# 1-3circuits.net
KiCad netlist of a schematic drawn in EasyEDA
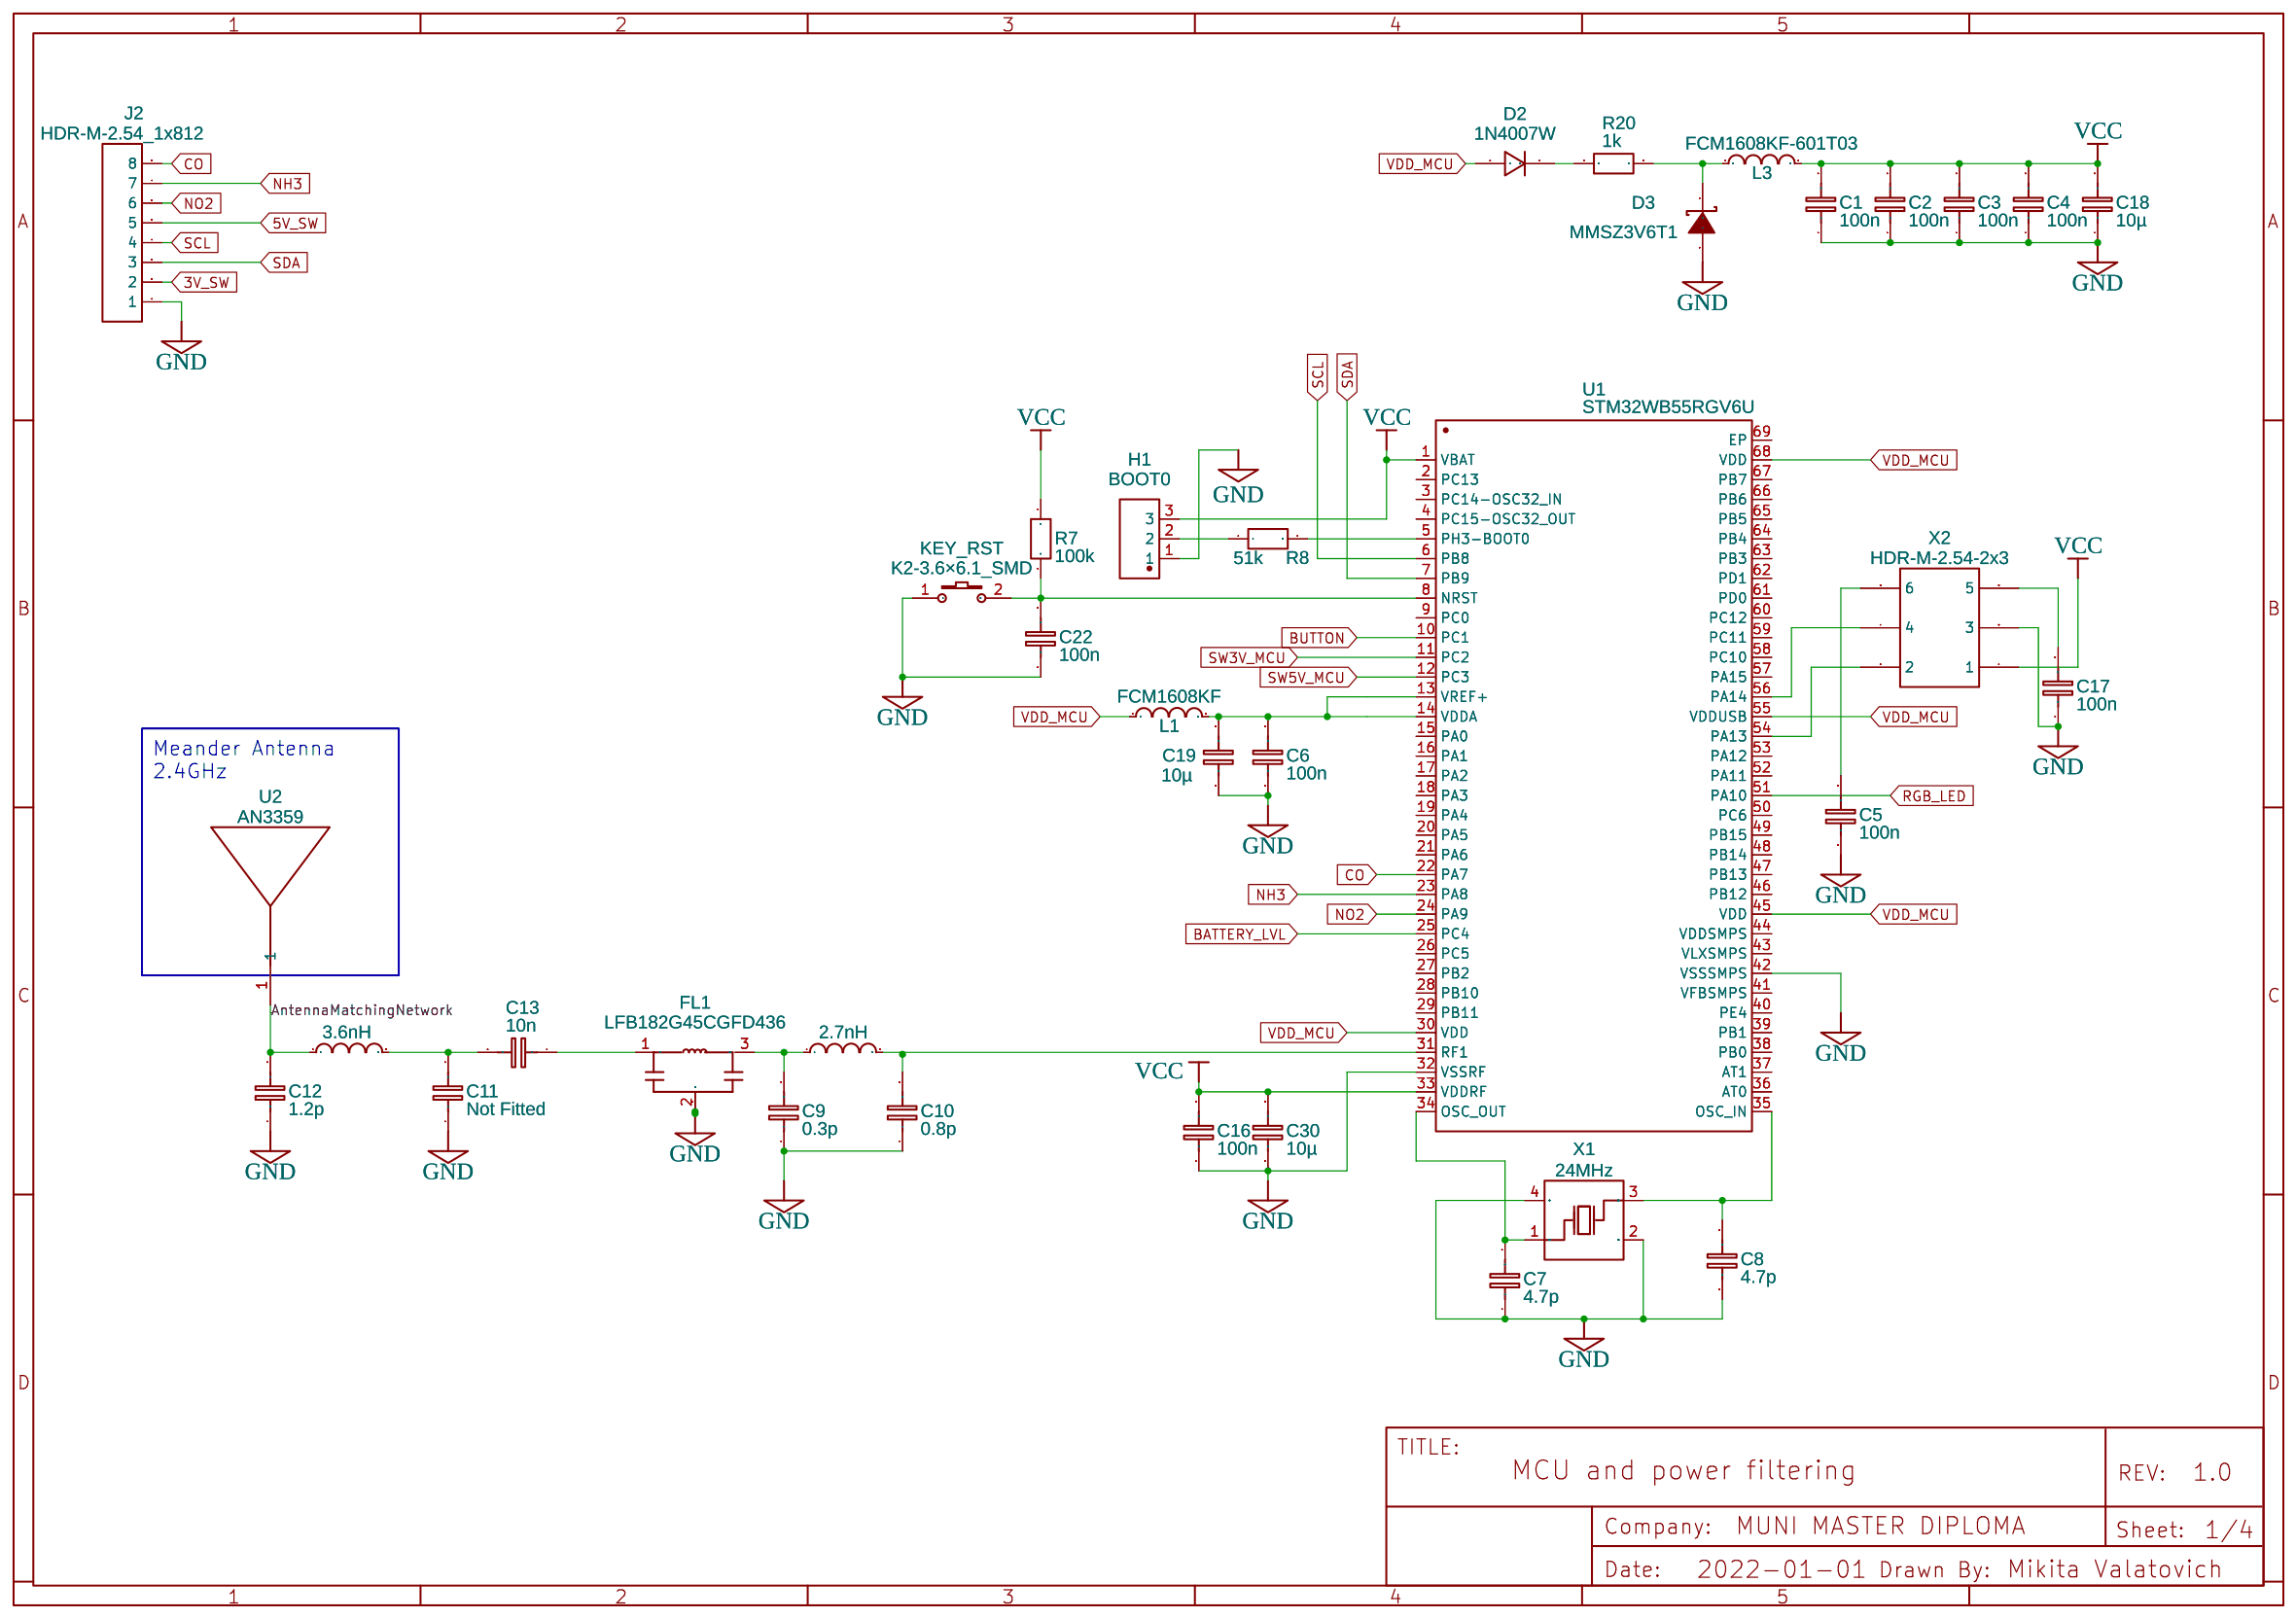
[diagram p0: mcu]
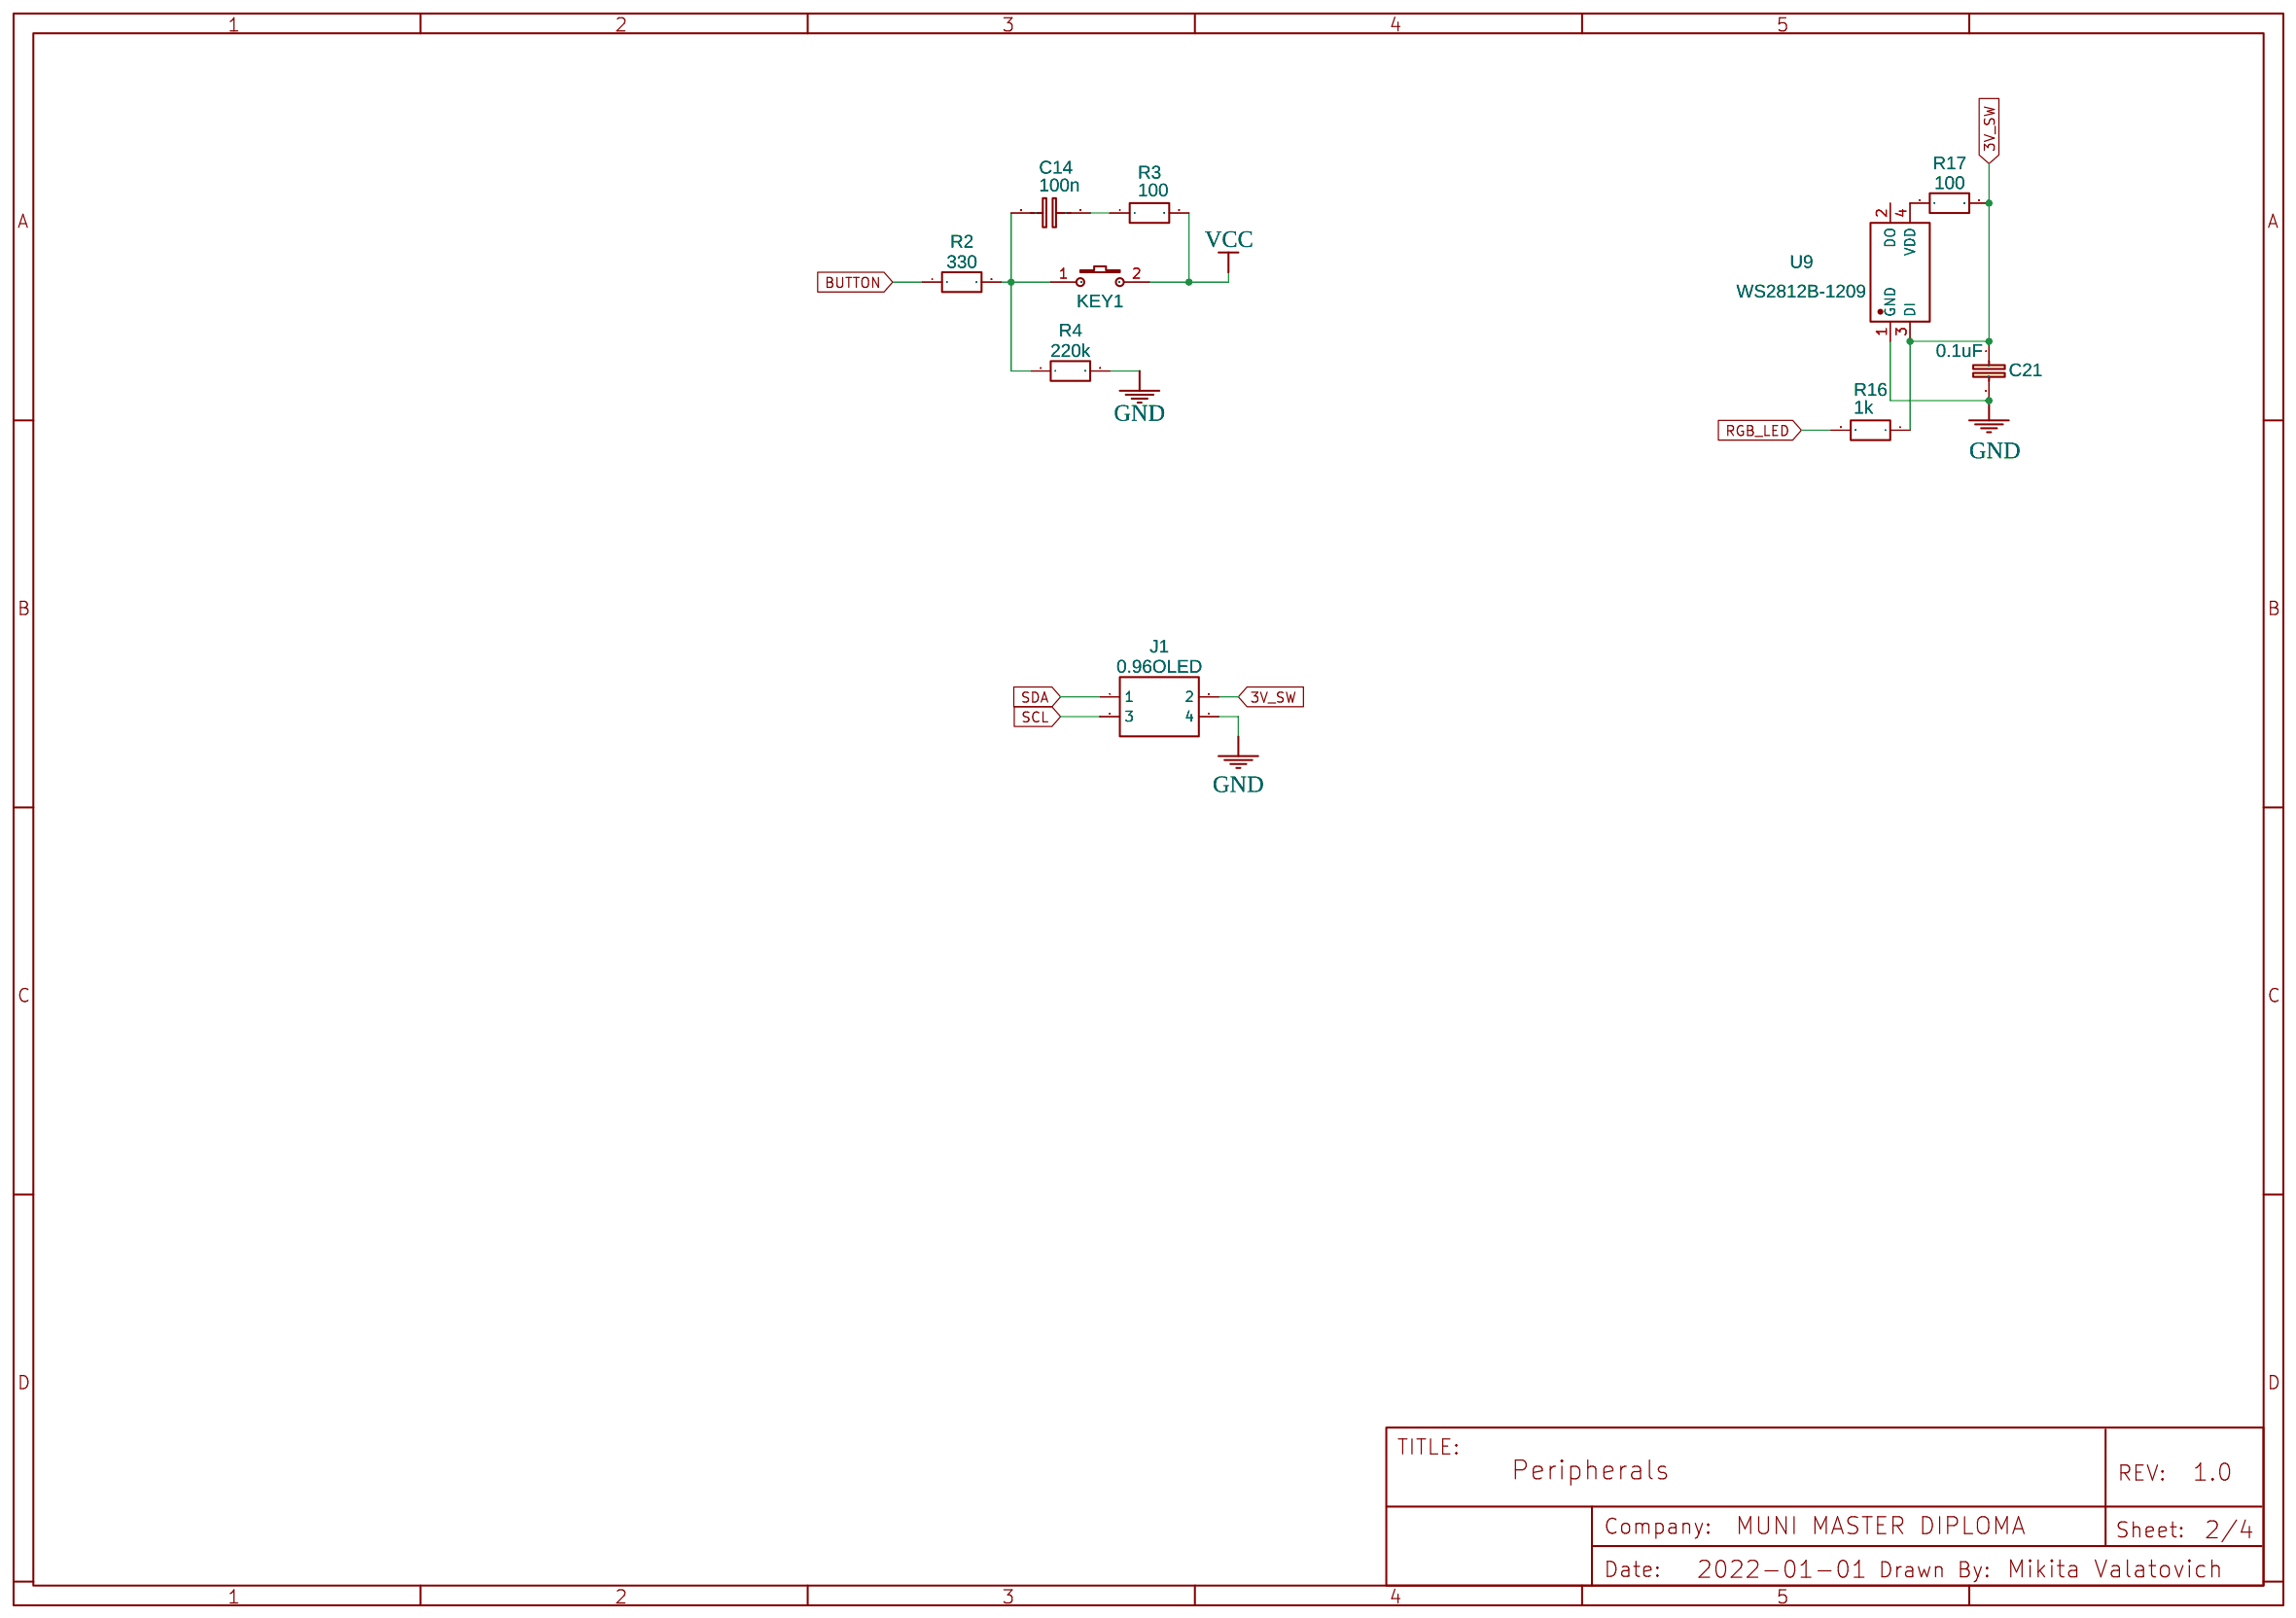
[diagram p1: peripherals]
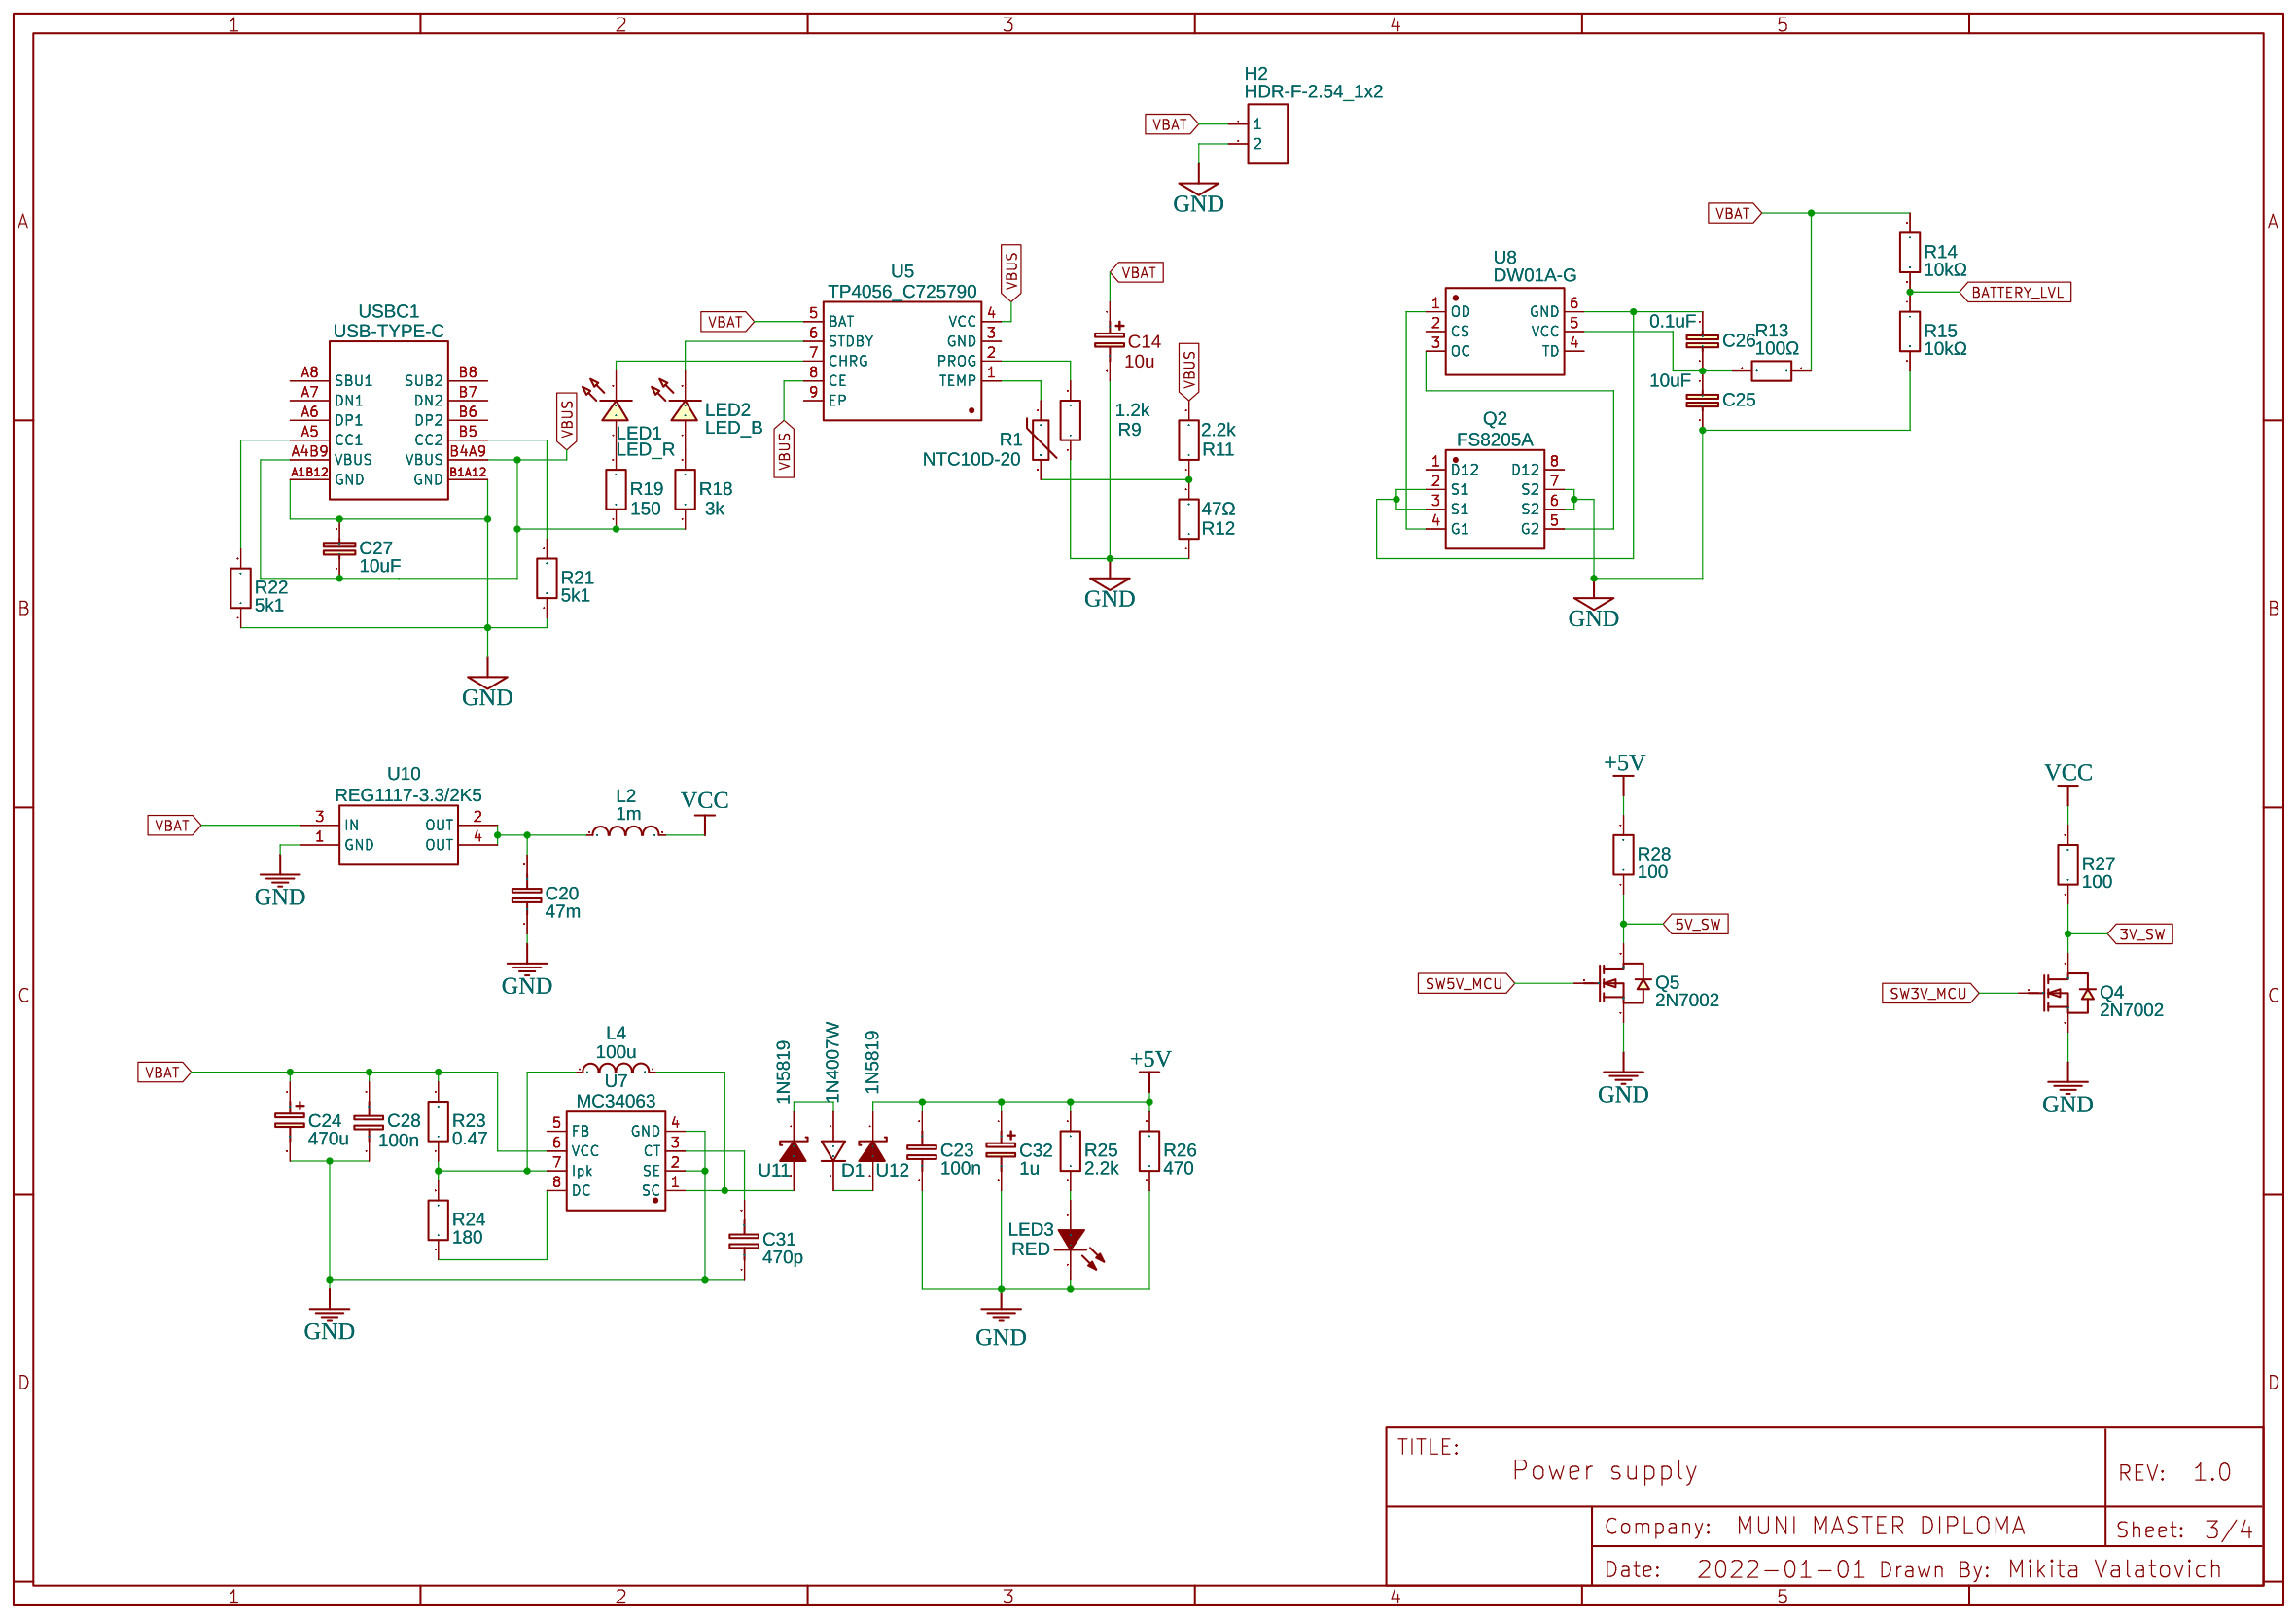
[diagram p2: power_supply]

(export (version "E")
  (design (tool "Eeschema 10.0.6"))
  (components
    (comp (ref "C1") (value "100n") (libsource (lib "") (part "C_0603_EU_1")))
    (comp (ref "C2") (value "100n") (libsource (lib "") (part "C_0603_EU_1")))
    (comp (ref "C3") (value "100n") (libsource (lib "") (part "C_0603_EU_1")))
    (comp (ref "C4") (value "100n") (libsource (lib "") (part "C_0603_EU_1")))
    (comp (ref "C5") (value "100n") (libsource (lib "") (part "C_0603_EU")))
    (comp (ref "C6") (value "100n") (libsource (lib "") (part "C_0603_EU")))
    (comp (ref "C7") (value "4.7p") (libsource (lib "") (part "C_0603_EU")))
    (comp (ref "C8") (value "4.7p") (libsource (lib "") (part "C_0603_EU")))
    (comp (ref "C9") (value "0.3p") (libsource (lib "") (part "C_0603_EU_3")))
    (comp (ref "C10") (value "0.8p") (libsource (lib "") (part "C_0603_EU_3")))
    (comp (ref "C11") (value "Not Fitted") (libsource (lib "") (part "C_0603_EU_3")))
    (comp (ref "C12") (value "1.2p") (libsource (lib "") (part "C_0603_EU_3")))
    (comp (ref "C13") (value "10n") (libsource (lib "") (part "C_0603_EU_2")))
    (comp (ref "C16") (value "100n") (libsource (lib "") (part "C_0603_EU")))
    (comp (ref "C17") (value "100n") (libsource (lib "") (part "C_0603_EU")))
    (comp (ref "C18") (value "10µ") (libsource (lib "") (part "C_0603_EU_1")))
    (comp (ref "C19") (value "10µ") (libsource (lib "") (part "C_0603_EU")))
    (comp (ref "C22") (value "100n") (libsource (lib "") (part "C_0603_EU")))
    (comp (ref "C30") (value "10µ") (libsource (lib "") (part "C_0603_EU")))
    (comp (ref "D2")
      (value "1N4007W")
      (fields (field (name "BOM_Supplier Part") "C328592"))
      (libsource (lib "") (part "1N4007W"))
    )
    (comp (ref "D3")
      (value "MMSZ3V6T1")
      (fields
        (field (name "BOM_Manufacturer Part") "DIODEZENER3.3V500MWSOD-523")
        (field (name "BOM_Supplier Part") "C9900023612")
      )
      (libsource (lib "") (part "DIODEZENER3.3V500MWSOD-523"))
    )
    (comp (ref "FL1") (value "LFB182G45CGFD436") (libsource (lib "") (part "LFB182G45CGFD436")))
    (comp (ref "H1")
      (value "BOOT0")
      (fields
        (field (name "BOM_Manufacturer Part") "PZ254-1-03-Z-8.5")
        (field (name "BOM_Supplier Part") "C2894926")
      )
      (libsource (lib "") (part "PZ254-1-03-Z-8.5"))
    )
    (comp (ref "J2")
      (value "HDR-M-2.54_1x812")
      (fields (field (name "BOM_Supplier Part") "C190820"))
      (libsource (lib "") (part "HDR-M-2.54_1x812"))
    )
    (comp (ref "KEY_RST")
      (value "K2-3.6×6.1_SMD")
      (fields
        (field (name "BOM_Manufacturer Part") "K2-1107ST-A4SW-06")
        (field (name "BOM_Supplier Part") "C118141")
      )
      (libsource (lib "") (part "K2-3.6×6.1_SMD"))
    )
    (comp (ref "L")
      (value "3.6nH")
      (fields
        (field (name "BOM_Manufacturer Part") "LQG15HS3N6S02D")
        (field (name "BOM_Supplier Part") "81-LQG15HS3N6S02D")
      )
      (libsource (lib "") (part "LQG15HS3N6S02D"))
    )
    (comp (ref "L1")
      (value "FCM1608KF")
      (fields
        (field (name "BOM_Manufacturer Part") "FCM1608KF-601T03")
        (field (name "BOM_Supplier Part") "C141723")
      )
      (libsource (lib "") (part "FCM1608KF-601T03"))
    )
    (comp (ref "L3")
      (value "FCM1608KF-601T03")
      (fields (field (name "BOM_Supplier Part") "C141723"))
      (libsource (lib "") (part "FCM1608KF-601T03"))
    )
    (comp (ref "NO")
      (value "2.7nH")
      (fields
        (field (name "BOM_Manufacturer Part") "LQG15HS2N7S02D")
        (field (name "BOM_Supplier Part") "81-LQG15HS2N7S02D")
      )
      (libsource (lib "") (part "LQG15HS2N7S02D"))
    )
    (comp (ref "R7") (value "100k") (libsource (lib "") (part "R_0603_EU")))
    (comp (ref "R8") (value "51k") (libsource (lib "") (part "R_0603_EU_1")))
    (comp (ref "R20") (value "1k") (libsource (lib "") (part "R_0603_EU_1")))
    (comp (ref "U1")
      (value "STM32WB55RGV6U")
      (fields (field (name "BOM_Supplier Part") "C1558433"))
      (libsource (lib "") (part "STM32WB55RGV6U"))
    )
    (comp (ref "U2") (value "AN3359") (libsource (lib "") (part "AN3359")))
    (comp (ref "X1")
      (value "24MHz")
      (fields
        (field (name "BOM_Manufacturer Part") "ABM8AIG-24.000MHZ-R40-4-T")
        (field (name "BOM_Supplier Part") "C1986620")
      )
      (libsource (lib "") (part "ABM8AIG-24.000MHZ-R40-4-T"))
    )
    (comp (ref "X2") (value "HDR-M-2.54-2x3") (libsource (lib "") (part "HDR-M-2.54-2x3")))
    (comp (ref "C14") (value "100n") (libsource (lib "") (part "C_0603_EU")))
    (comp (ref "C21") (value "0.1uF") (libsource (lib "") (part "0.1UF-25V(+80_-20%)(0603)")))
    (comp (ref "J1")
      (value "0.96OLED")
      (fields (field (name "BOM_Supplier Part") "C66690"))
      (libsource (lib "") (part "HDR-M-2.54_2x2"))
    )
    (comp (ref "KEY1")
      (value "K2-3.6×6.1_SMD")
      (fields
        (field (name "BOM_Manufacturer Part") "K2-1107ST-A4SW-06")
        (field (name "BOM_Supplier Part") "C118141")
      )
      (libsource (lib "") (part "K2-3.6×6.1_SMD"))
    )
    (comp (ref "R2") (value "330") (libsource (lib "") (part "R_0603_EU")))
    (comp (ref "R3") (value "100") (libsource (lib "") (part "R_0603_EU")))
    (comp (ref "R4") (value "220k") (libsource (lib "") (part "R_0603_EU")))
    (comp (ref "R16")
      (value "1k")
      (fields
        (field (name "BOM_Manufacturer Part") "TCTR0603F47K0F3960T")
        (field (name "BOM_Supplier Part") "C525388")
      )
      (libsource (lib "") (part "TCTR0603F47K0F3960T_1"))
    )
    (comp (ref "R17")
      (value "100")
      (fields
        (field (name "BOM_Manufacturer Part") "TCTR0603F47K0F3960T")
        (field (name "BOM_Supplier Part") "C525388")
      )
      (libsource (lib "") (part "TCTR0603F47K0F3960T"))
    )
    (comp (ref "U9")
      (value "WS2812B-1209")
      (fields (field (name "BOM_Supplier Part") "C2835111"))
      (libsource (lib "") (part "WS2812B-1209"))
    )
    (comp (ref "C20") (value "47m") (libsource (lib "") (part "C_0603_EU")))
    (comp (ref "C23") (value "100n") (libsource (lib "") (part "C_0603_EU")))
    (comp (ref "C24") (value "470u") (libsource (lib "") (part "C_Tan_SMD_A_EU_1")))
    (comp (ref "C25") (value "10uF") (libsource (lib "") (part "0.1UF-25V(+80_-20%)(0603)")))
    (comp (ref "C26") (value "0.1uF") (libsource (lib "") (part "0.1UF-25V(+80_-20%)(0603)")))
    (comp (ref "C27") (value "10uF") (libsource (lib "") (part "0.1UF-25V(+80_-20%)(0603)_1")))
    (comp (ref "C28") (value "100n") (libsource (lib "") (part "C_0603_EU")))
    (comp (ref "C31") (value "470p") (libsource (lib "") (part "C_0603_EU")))
    (comp (ref "C32") (value "1u") (libsource (lib "") (part "C_Tan_SMD_A_EU")))
    (comp (ref "D1")
      (value "1N4007W")
      (fields (field (name "BOM_Supplier Part") "C328592"))
      (libsource (lib "") (part "1N4007W"))
    )
    (comp (ref "H2")
      (value "HDR-F-2.54_1x2")
      (fields (field (name "BOM_Supplier Part") "C49661"))
      (libsource (lib "") (part "HDR-F-2.54_1x2"))
    )
    (comp (ref "L2") (value "1m") (libsource (lib "") (part "L0603_US")))
    (comp (ref "L4") (value "100u") (libsource (lib "") (part "L0603_US")))
    (comp (ref "LED1")
      (value "LED_R")
      (fields
        (field (name "BOM_Manufacturer Part") "19-217/R6C-AL1M2VY/3T")
        (field (name "BOM_Supplier Part") "C72044")
      )
      (libsource (lib "") (part "LED-0603_R"))
    )
    (comp (ref "LED2")
      (value "LED_B")
      (fields
        (field (name "BOM_Manufacturer Part") "19-217/BHC-ZL1M2RY/3T")
        (field (name "BOM_Supplier Part") "C72041")
      )
      (libsource (lib "") (part "LED-0603_B"))
    )
    (comp (ref "LED3")
      (value "RED")
      (fields
        (field (name "BOM_Manufacturer Part") "whiteLEDSMD")
        (field (name "BOM_Supplier Part") "C34499")
      )
      (libsource (lib "") (part "whiteLEDSMD"))
    )
    (comp (ref "Q2")
      (value "FS8205A")
      (fields (field (name "BOM_Supplier Part") "C16052"))
      (libsource (lib "") (part "FS8205A"))
    )
    (comp (ref "Q4")
      (value "2N7002")
      (fields (field (name "BOM_Manufacturer Part") "2N7002,215") (field (name "BOM_Supplier Part") "C65189"))
      (libsource (lib "") (part "2N7002"))
    )
    (comp (ref "Q5")
      (value "2N7002")
      (fields (field (name "BOM_Manufacturer Part") "2N7002,215") (field (name "BOM_Supplier Part") "C65189"))
      (libsource (lib "") (part "2N7002"))
    )
    (comp (ref "R1")
      (value "NTC10D-20")
      (fields
        (field (name "BOM_Manufacturer Part") "NTCThermistor")
        (field (name "BOM_Supplier Part") "C42975")
      )
      (libsource (lib "") (part "Thermistor"))
    )
    (comp (ref "R9")
      (value "1.2k")
      (fields
        (field (name "BOM_Manufacturer Part") "TCTR0603F47K0F3960T")
        (field (name "BOM_Supplier Part") "C525388")
      )
      (libsource (lib "") (part "TCTR0603F47K0F3960T"))
    )
    (comp (ref "R11")
      (value "2.2k")
      (fields
        (field (name "BOM_Manufacturer Part") "TCTR0603F47K0F3960T")
        (field (name "BOM_Supplier Part") "C525388")
      )
      (libsource (lib "") (part "TCTR0603F47K0F3960T"))
    )
    (comp (ref "R12")
      (value "47Ω")
      (fields
        (field (name "BOM_Manufacturer Part") "TCTR0603F47K0F3960T")
        (field (name "BOM_Supplier Part") "C525388")
      )
      (libsource (lib "") (part "TCTR0603F47K0F3960T"))
    )
    (comp (ref "R13")
      (value "100Ω")
      (fields
        (field (name "BOM_Manufacturer Part") "TCTR0603F47K0F3960T")
        (field (name "BOM_Supplier Part") "C525388")
      )
      (libsource (lib "") (part "TCTR0603F47K0F3960T_1"))
    )
    (comp (ref "R14")
      (value "10kΩ")
      (fields
        (field (name "BOM_Manufacturer Part") "TCTR0603F47K0F3960T")
        (field (name "BOM_Supplier Part") "C525388")
      )
      (libsource (lib "") (part "TCTR0603F47K0F3960T_2"))
    )
    (comp (ref "R15")
      (value "10kΩ")
      (fields
        (field (name "BOM_Manufacturer Part") "TCTR0603F47K0F3960T")
        (field (name "BOM_Supplier Part") "C525388")
      )
      (libsource (lib "") (part "TCTR0603F47K0F3960T_2"))
    )
    (comp (ref "R18")
      (value "3k")
      (fields
        (field (name "BOM_Manufacturer Part") "TCTR0603F47K0F3960T")
        (field (name "BOM_Supplier Part") "C525388")
      )
      (libsource (lib "") (part "TCTR0603F47K0F3960T"))
    )
    (comp (ref "R19")
      (value "150")
      (fields
        (field (name "BOM_Manufacturer Part") "TCTR0603F47K0F3960T")
        (field (name "BOM_Supplier Part") "C525388")
      )
      (libsource (lib "") (part "TCTR0603F47K0F3960T"))
    )
    (comp (ref "R21") (value "5k1") (libsource (lib "") (part "R_0603_EU")))
    (comp (ref "R22") (value "5k1") (libsource (lib "") (part "R_0603_EU")))
    (comp (ref "R23") (value "0.47") (libsource (lib "") (part "R_0603_EU")))
    (comp (ref "R24") (value "180") (libsource (lib "") (part "R_0603_EU")))
    (comp (ref "R25") (value "2.2k") (libsource (lib "") (part "R_0603_EU")))
    (comp (ref "R26") (value "470") (libsource (lib "") (part "R_0603_EU")))
    (comp (ref "R27") (value "100") (libsource (lib "") (part "R_0603_EU")))
    (comp (ref "R28") (value "100") (libsource (lib "") (part "R_0603_EU")))
    (comp (ref "U5")
      (value "TP4056_C725790")
      (fields (field (name "BOM_Manufacturer Part") "TP4056") (field (name "BOM_Supplier Part") "C725790"))
      (libsource (lib "") (part "TP4056_C725790"))
    )
    (comp (ref "U6")
      (value "electrolitic_cap_th_to_smd")
      (libsource (lib "") (part "electrolitic_cap_th_to_smd"))
    )
    (comp (ref "U7")
      (value "MC34063")
      (fields
        (field (name "BOM_Manufacturer Part") "MC34063ADR")
        (field (name "BOM_Supplier Part") "C3014308")
      )
      (libsource (lib "") (part "MC34063ADR_C3014308"))
    )
    (comp (ref "U8")
      (value "DW01A-G")
      (fields (field (name "BOM_Supplier Part") "C61503"))
      (libsource (lib "") (part "DW01A-G"))
    )
    (comp (ref "U10")
      (value "REG1117-3.3/2K5")
      (fields (field (name "BOM_Supplier Part") "C139396"))
      (libsource (lib "") (part "REG1117-3.3/2K5"))
    )
    (comp (ref "U11")
      (value "1N5819")
      (fields (field (name "BOM_Supplier Part") "C3039965"))
      (libsource (lib "") (part "1N5819_C3039965"))
    )
    (comp (ref "U12")
      (value "1N5819")
      (fields (field (name "BOM_Supplier Part") "C3039965"))
      (libsource (lib "") (part "1N5819_C3039965"))
    )
    (comp (ref "USBC1")
      (value "USB-TYPE-C")
      (fields
        (field (name "BOM_Manufacturer Part") "TYPE-C-31-M-14")
        (field (name "BOM_Supplier Part") "C223907")
      )
      (libsource (lib "") (part "USB-TYPE-C"))
    )
  )
  (nets
    (net (code "1") (name "+5V") (class "Default")
      (node (ref "C23") (pin "2") (pinfunction "2_2") (pintype "unspecified"))
      (node (ref "C32") (pin "1") (pinfunction "1_1") (pintype "unspecified"))
      (node (ref "R25") (pin "2") (pinfunction "2_2") (pintype "unspecified"))
      (node (ref "R26") (pin "2") (pinfunction "2_2") (pintype "unspecified"))
      (node (ref "R28") (pin "2") (pinfunction "2_2") (pintype "unspecified"))
      (node (ref "U12") (pin "1") (pinfunction "K_1") (pintype "unspecified"))
    )
    (net (code "2") (name "3V_SW") (class "Default")
      (node (ref "C21") (pin "1") (pinfunction "1_1") (pintype "unspecified"))
      (node (ref "J1") (pin "2") (pinfunction "2_2") (pintype "input"))
      (node (ref "J2") (pin "2") (pinfunction "2_2") (pintype "unspecified"))
      (node (ref "Q4") (pin "3") (pinfunction "D_3") (pintype "unspecified"))
      (node (ref "R16") (pin "1") (pinfunction "1_1") (pintype "unspecified"))
      (node (ref "R17") (pin "2") (pinfunction "2_2") (pintype "unspecified"))
      (node (ref "R27") (pin "1") (pinfunction "1_1") (pintype "unspecified"))
      (node (ref "U9") (pin "3") (pinfunction "DI_3") (pintype "unspecified"))
    )
    (net (code "3") (name "5V_SW") (class "Default")
      (node (ref "J2") (pin "5") (pinfunction "5_5") (pintype "unspecified"))
      (node (ref "Q5") (pin "3") (pinfunction "D_3") (pintype "unspecified"))
      (node (ref "R28") (pin "1") (pinfunction "1_1") (pintype "unspecified"))
    )
    (net (code "4") (name "AntennaMatchingNetwork") (class "Default")
      (node (ref "C12") (pin "2") (pinfunction "2_2") (pintype "unspecified"))
      (node (ref "L") (pin "1") (pinfunction "1_1") (pintype "unspecified"))
      (node (ref "U2") (pin "1") (pinfunction "1_1") (pintype "unspecified"))
    )
    (net (code "5") (name "BATTERY_LVL") (class "Default")
      (node (ref "R14") (pin "2") (pinfunction "2_2") (pintype "unspecified"))
      (node (ref "R15") (pin "1") (pinfunction "1_1") (pintype "unspecified"))
      (node (ref "U1") (pin "25") (pinfunction "PC4_25") (pintype "unspecified"))
    )
    (net (code "6") (name "BUTTON") (class "Default")
      (node (ref "R2") (pin "1") (pinfunction "1_1") (pintype "unspecified"))
      (node (ref "U1") (pin "10") (pinfunction "PC1_10") (pintype "unspecified"))
    )
    (net (code "7") (name "CO") (class "Default")
      (node (ref "J2") (pin "8") (pinfunction "8_8") (pintype "unspecified"))
      (node (ref "U1") (pin "22") (pinfunction "PA7_22") (pintype "unspecified"))
    )
    (net (code "8") (name "GND") (class "Default")
      (node (ref "C1") (pin "1") (pinfunction "1_1") (pintype "unspecified"))
      (node (ref "C10") (pin "1") (pinfunction "1_1") (pintype "unspecified"))
      (node (ref "C11") (pin "1") (pinfunction "1_1") (pintype "unspecified"))
      (node (ref "C12") (pin "1") (pinfunction "1_1") (pintype "unspecified"))
      (node (ref "C16") (pin "1") (pinfunction "1_1") (pintype "unspecified"))
      (node (ref "C17") (pin "1") (pinfunction "1_1") (pintype "unspecified"))
      (node (ref "C18") (pin "1") (pinfunction "1_1") (pintype "unspecified"))
      (node (ref "C19") (pin "1") (pinfunction "1_1") (pintype "unspecified"))
      (node (ref "C2") (pin "1") (pinfunction "1_1") (pintype "unspecified"))
      (node (ref "C20") (pin "1") (pinfunction "1_1") (pintype "unspecified"))
      (node (ref "C21") (pin "2") (pinfunction "2_2") (pintype "unspecified"))
      (node (ref "C22") (pin "1") (pinfunction "1_1") (pintype "unspecified"))
      (node (ref "C23") (pin "1") (pinfunction "1_1") (pintype "unspecified"))
      (node (ref "C24") (pin "2") (pinfunction "2_2") (pintype "unspecified"))
      (node (ref "C25") (pin "2") (pinfunction "2_2") (pintype "unspecified"))
      (node (ref "C27") (pin "2") (pinfunction "2_2") (pintype "unspecified"))
      (node (ref "C28") (pin "1") (pinfunction "1_1") (pintype "unspecified"))
      (node (ref "C3") (pin "1") (pinfunction "1_1") (pintype "unspecified"))
      (node (ref "C30") (pin "1") (pinfunction "1_1") (pintype "unspecified"))
      (node (ref "C31") (pin "1") (pinfunction "1_1") (pintype "unspecified"))
      (node (ref "C32") (pin "2") (pinfunction "2_2") (pintype "unspecified"))
      (node (ref "C4") (pin "1") (pinfunction "1_1") (pintype "unspecified"))
      (node (ref "C5") (pin "1") (pinfunction "1_1") (pintype "unspecified"))
      (node (ref "C6") (pin "1") (pinfunction "1_1") (pintype "unspecified"))
      (node (ref "C7") (pin "1") (pinfunction "1_1") (pintype "unspecified"))
      (node (ref "C8") (pin "1") (pinfunction "1_1") (pintype "unspecified"))
      (node (ref "C9") (pin "1") (pinfunction "1_1") (pintype "unspecified"))
      (node (ref "D3") (pin "2") (pinfunction "A_2") (pintype "unspecified"))
      (node (ref "FL1") (pin "2") (pinfunction "GND_2") (pintype "bidirectional"))
      (node (ref "FL1") (pin "2_1") (pinfunction "GND_2_1") (pintype "bidirectional"))
      (node (ref "H1") (pin "1") (pinfunction "1_1") (pintype "unspecified"))
      (node (ref "H2") (pin "2") (pinfunction "2_2") (pintype "input"))
      (node (ref "J1") (pin "4") (pinfunction "4_4") (pintype "input"))
      (node (ref "J2") (pin "1") (pinfunction "1_1") (pintype "unspecified"))
      (node (ref "KEY_RST") (pin "1") (pinfunction "1_1") (pintype "unspecified"))
      (node (ref "LED3") (pin "2") (pinfunction "K_2") (pintype "unspecified"))
      (node (ref "Q2") (pin "6") (pinfunction "S2_6") (pintype "unspecified"))
      (node (ref "Q2") (pin "7") (pinfunction "S2_7") (pintype "unspecified"))
      (node (ref "Q4") (pin "2") (pinfunction "S_2") (pintype "unspecified"))
      (node (ref "Q5") (pin "2") (pinfunction "S_2") (pintype "unspecified"))
      (node (ref "R12") (pin "1") (pinfunction "1_1") (pintype "unspecified"))
      (node (ref "R15") (pin "2") (pinfunction "2_2") (pintype "unspecified"))
      (node (ref "R21") (pin "1") (pinfunction "1_1") (pintype "unspecified"))
      (node (ref "R22") (pin "1") (pinfunction "1_1") (pintype "unspecified"))
      (node (ref "R26") (pin "1") (pinfunction "1_1") (pintype "unspecified"))
      (node (ref "R4") (pin "2") (pinfunction "2_2") (pintype "unspecified"))
      (node (ref "R9") (pin "1") (pinfunction "1_1") (pintype "unspecified"))
      (node (ref "U1") (pin "32") (pinfunction "VSSRF_32") (pintype "unspecified"))
      (node (ref "U1") (pin "42") (pinfunction "VSSSMPS_42") (pintype "unspecified"))
      (node (ref "U10") (pin "1") (pinfunction "GND_1") (pintype "passive"))
      (node (ref "U6") (pin "2") (pinfunction "2_2") (pintype "unspecified"))
      (node (ref "U7") (pin "2") (pinfunction "SE_2") (pintype "unspecified"))
      (node (ref "U7") (pin "4") (pinfunction "GND_4") (pintype "unspecified"))
      (node (ref "U9") (pin "1") (pinfunction "GND_1") (pintype "unspecified"))
      (node (ref "USBC1") (pin "A1B12") (pinfunction "GND_A1B12") (pintype "unspecified"))
      (node (ref "USBC1") (pin "B1A12") (pinfunction "GND_B1A12") (pintype "unspecified"))
      (node (ref "X1") (pin "2") (pinfunction "GND_2") (pintype "unspecified"))
      (node (ref "X1") (pin "4") (pinfunction "GND_4") (pintype "unspecified"))
      (node (ref "X2") (pin "3") (pinfunction "3_3") (pintype "unspecified"))
    )
    (net (code "9") (name "NH3") (class "Default")
      (node (ref "J2") (pin "7") (pinfunction "7_7") (pintype "unspecified"))
      (node (ref "U1") (pin "23") (pinfunction "PA8_23") (pintype "unspecified"))
    )
    (net (code "10") (name "NO2") (class "Default")
      (node (ref "J2") (pin "6") (pinfunction "6_6") (pintype "unspecified"))
      (node (ref "U1") (pin "24") (pinfunction "PA9_24") (pintype "unspecified"))
    )
    (net (code "11") (name "Net-(C5-Pad2)") (class "Default")
      (node (ref "C5") (pin "2") (pinfunction "2_2") (pintype "unspecified"))
      (node (ref "X2") (pin "6") (pinfunction "6_6") (pintype "unspecified"))
    )
    (net (code "12") (name "Net-(C11-Pad2)") (class "Default")
      (node (ref "C11") (pin "2") (pinfunction "2_2") (pintype "unspecified"))
      (node (ref "C13") (pin "2") (pinfunction "2_2") (pintype "unspecified"))
      (node (ref "L") (pin "2") (pinfunction "2_2") (pintype "unspecified"))
    )
    (net (code "13") (name "Net-(C14-Pad1)") (class "Default")
      (node (ref "C14") (pin "1") (pinfunction "1_1") (pintype "unspecified"))
      (node (ref "KEY1") (pin "1") (pinfunction "1_1") (pintype "unspecified"))
      (node (ref "R2") (pin "2") (pinfunction "2_2") (pintype "unspecified"))
      (node (ref "R4") (pin "1") (pinfunction "1_1") (pintype "unspecified"))
    )
    (net (code "14") (name "Net-(C14-Pad2)") (class "Default")
      (node (ref "C14") (pin "2") (pinfunction "2_2") (pintype "unspecified"))
      (node (ref "R3") (pin "1") (pinfunction "1_1") (pintype "unspecified"))
    )
    (net (code "15") (name "Net-(C17-Pad2)") (class "Default")
      (node (ref "C17") (pin "2") (pinfunction "2_2") (pintype "unspecified"))
      (node (ref "X2") (pin "5") (pinfunction "5_5") (pintype "unspecified"))
    )
    (net (code "16") (name "Net-(C20-Pad2)") (class "Default")
      (node (ref "C20") (pin "2") (pinfunction "2_2") (pintype "unspecified"))
      (node (ref "L2") (pin "1") (pinfunction "1_1") (pintype "unspecified"))
      (node (ref "U10") (pin "2") (pinfunction "OUT_2") (pintype "passive"))
      (node (ref "U10") (pin "4") (pinfunction "OUT_4") (pintype "passive"))
    )
    (net (code "17") (name "Net-(D2-Pad1)") (class "Default")
      (node (ref "D2") (pin "1") (pinfunction "1_1") (pintype "unspecified"))
      (node (ref "R20") (pin "1") (pinfunction "1_1") (pintype "unspecified"))
    )
    (net (code "18") (name "Net-(D3-K)") (class "Default")
      (node (ref "D3") (pin "1") (pinfunction "K_1") (pintype "unspecified"))
      (node (ref "L3") (pin "1") (pinfunction "1_1") (pintype "unspecified"))
      (node (ref "R20") (pin "2") (pinfunction "2_2") (pintype "unspecified"))
    )
    (net (code "19") (name "Net-(FL1-IN)") (class "Default")
      (node (ref "C13") (pin "1") (pinfunction "1_1") (pintype "unspecified"))
      (node (ref "FL1") (pin "1") (pinfunction "IN_1") (pintype "bidirectional"))
    )
    (net (code "20") (name "Net-(FL1-OUT)") (class "Default")
      (node (ref "C9") (pin "2") (pinfunction "2_2") (pintype "unspecified"))
      (node (ref "FL1") (pin "3") (pinfunction "OUT_3") (pintype "bidirectional"))
      (node (ref "NO") (pin "1") (pinfunction "1_1") (pintype "unspecified"))
    )
    (net (code "21") (name "Net-(H1-Pad2)") (class "Default")
      (node (ref "H1") (pin "2") (pinfunction "2_2") (pintype "unspecified"))
      (node (ref "R8") (pin "1") (pinfunction "1_1") (pintype "unspecified"))
    )
    (net (code "22") (name "Net-(LED1-Pad1)") (class "Default")
      (node (ref "LED1") (pin "1") (pinfunction "1_1") (pintype "unspecified"))
      (node (ref "R19") (pin "2") (pinfunction "2_2") (pintype "unspecified"))
    )
    (net (code "23") (name "Net-(LED2-Pad1)") (class "Default")
      (node (ref "LED2") (pin "1") (pinfunction "1_1") (pintype "unspecified"))
      (node (ref "R18") (pin "2") (pinfunction "2_2") (pintype "unspecified"))
    )
    (net (code "24") (name "Net-(LED3-A)") (class "Default")
      (node (ref "LED3") (pin "1") (pinfunction "A_1") (pintype "unspecified"))
      (node (ref "R25") (pin "1") (pinfunction "1_1") (pintype "unspecified"))
    )
    (net (code "25") (name "Net-(Q2-G1)") (class "Default")
      (node (ref "Q2") (pin "4") (pinfunction "G1_4") (pintype "unspecified"))
      (node (ref "U8") (pin "1") (pinfunction "OD_1") (pintype "unspecified"))
    )
    (net (code "26") (name "Net-(Q2-G2)") (class "Default")
      (node (ref "Q2") (pin "5") (pinfunction "G2_5") (pintype "unspecified"))
      (node (ref "U8") (pin "3") (pinfunction "OC_3") (pintype "unspecified"))
    )
    (net (code "27") (name "Net-(R1-Pad2)") (class "Default")
      (node (ref "R1") (pin "2") (pinfunction "2_2") (pintype "input"))
      (node (ref "R11") (pin "1") (pinfunction "1_1") (pintype "unspecified"))
      (node (ref "R12") (pin "2") (pinfunction "2_2") (pintype "unspecified"))
    )
    (net (code "28") (name "Net-(U1-NRST)") (class "Default")
      (node (ref "C22") (pin "2") (pinfunction "2_2") (pintype "unspecified"))
      (node (ref "KEY_RST") (pin "2") (pinfunction "2_2") (pintype "unspecified"))
      (node (ref "R7") (pin "2") (pinfunction "2_2") (pintype "unspecified"))
      (node (ref "U1") (pin "8") (pinfunction "NRST_8") (pintype "unspecified"))
    )
    (net (code "29") (name "Net-(U1-OSC_IN)") (class "Default")
      (node (ref "C8") (pin "2") (pinfunction "2_2") (pintype "unspecified"))
      (node (ref "U1") (pin "35") (pinfunction "OSC_IN_35") (pintype "unspecified"))
      (node (ref "X1") (pin "3") (pinfunction "OSC2_3") (pintype "unspecified"))
    )
    (net (code "30") (name "Net-(U1-OSC_OUT)") (class "Default")
      (node (ref "C7") (pin "2") (pinfunction "2_2") (pintype "unspecified"))
      (node (ref "U1") (pin "34") (pinfunction "OSC_OUT_34") (pintype "unspecified"))
      (node (ref "X1") (pin "1") (pinfunction "OSC1_1") (pintype "unspecified"))
    )
    (net (code "31") (name "Net-(U1-PA13)") (class "Default")
      (node (ref "U1") (pin "54") (pinfunction "PA13_54") (pintype "unspecified"))
      (node (ref "X2") (pin "2") (pinfunction "2_2") (pintype "unspecified"))
    )
    (net (code "32") (name "Net-(U1-PA14)") (class "Default")
      (node (ref "U1") (pin "56") (pinfunction "PA14_56") (pintype "unspecified"))
      (node (ref "X2") (pin "4") (pinfunction "4_4") (pintype "unspecified"))
    )
    (net (code "33") (name "Net-(U1-PH3-BOOT0)") (class "Default")
      (node (ref "R8") (pin "2") (pinfunction "2_2") (pintype "unspecified"))
      (node (ref "U1") (pin "5") (pinfunction "PH3-BOOT0_5") (pintype "unspecified"))
    )
    (net (code "34") (name "Net-(U1-RF1)") (class "Default")
      (node (ref "C10") (pin "2") (pinfunction "2_2") (pintype "unspecified"))
      (node (ref "NO") (pin "2") (pinfunction "2_2") (pintype "unspecified"))
      (node (ref "U1") (pin "31") (pinfunction "RF1_31") (pintype "unspecified"))
    )
    (net (code "35") (name "Net-(U1-VDDA)") (class "Default")
      (node (ref "C19") (pin "2") (pinfunction "2_2") (pintype "unspecified"))
      (node (ref "C6") (pin "2") (pinfunction "2_2") (pintype "unspecified"))
      (node (ref "L1") (pin "2") (pinfunction "2_2") (pintype "unspecified"))
      (node (ref "U1") (pin "13") (pinfunction "VREF+_13") (pintype "unspecified"))
      (node (ref "U1") (pin "14") (pinfunction "VDDA_14") (pintype "unspecified"))
    )
    (net (code "36") (name "Net-(U5-CHRG)") (class "Default")
      (node (ref "LED1") (pin "2") (pinfunction "2_2") (pintype "unspecified"))
      (node (ref "U5") (pin "7") (pinfunction "CHRG_7") (pintype "unspecified"))
    )
    (net (code "37") (name "Net-(U5-PROG)") (class "Default")
      (node (ref "R9") (pin "2") (pinfunction "2_2") (pintype "unspecified"))
      (node (ref "U5") (pin "2") (pinfunction "PROG_2") (pintype "unspecified"))
    )
    (net (code "38") (name "Net-(U5-STDBY)") (class "Default")
      (node (ref "LED2") (pin "2") (pinfunction "2_2") (pintype "unspecified"))
      (node (ref "U5") (pin "6") (pinfunction "STDBY_6") (pintype "unspecified"))
    )
    (net (code "39") (name "Net-(U5-TEMP)") (class "Default")
      (node (ref "R1") (pin "1") (pinfunction "1_1") (pintype "input"))
      (node (ref "U5") (pin "1") (pinfunction "TEMP_1") (pintype "unspecified"))
    )
    (net (code "40") (name "Net-(U7-CT)") (class "Default")
      (node (ref "C31") (pin "2") (pinfunction "2_2") (pintype "unspecified"))
      (node (ref "U7") (pin "3") (pinfunction "CT_3") (pintype "unspecified"))
    )
    (net (code "41") (name "Net-(U7-DC)") (class "Default")
      (node (ref "R24") (pin "1") (pinfunction "1_1") (pintype "unspecified"))
      (node (ref "U7") (pin "8") (pinfunction "DC_8") (pintype "unspecified"))
    )
    (net (code "42") (name "Net-(U7-Ipk)") (class "Default")
      (node (ref "L4") (pin "1") (pinfunction "1_1") (pintype "unspecified"))
      (node (ref "R23") (pin "1") (pinfunction "1_1") (pintype "unspecified"))
      (node (ref "R24") (pin "2") (pinfunction "2_2") (pintype "unspecified"))
      (node (ref "U7") (pin "7") (pinfunction "Ipk_7") (pintype "unspecified"))
    )
    (net (code "43") (name "Net-(U8-GND)") (class "Default")
      (node (ref "C26") (pin "1") (pinfunction "1_1") (pintype "unspecified"))
      (node (ref "Q2") (pin "2") (pinfunction "S1_2") (pintype "unspecified"))
      (node (ref "Q2") (pin "3") (pinfunction "S1_3") (pintype "unspecified"))
      (node (ref "U8") (pin "6") (pinfunction "GND_6") (pintype "unspecified"))
    )
    (net (code "44") (name "Net-(U8-VCC)") (class "Default")
      (node (ref "C25") (pin "1") (pinfunction "1_1") (pintype "unspecified"))
      (node (ref "C26") (pin "2") (pinfunction "2_2") (pintype "unspecified"))
      (node (ref "R13") (pin "2") (pinfunction "2_2") (pintype "unspecified"))
      (node (ref "U8") (pin "5") (pinfunction "VCC_5") (pintype "unspecified"))
    )
    (net (code "45") (name "Net-(U9-VDD)") (class "Default")
      (node (ref "R17") (pin "1") (pinfunction "1_1") (pintype "unspecified"))
      (node (ref "U9") (pin "4") (pinfunction "VDD_4") (pintype "unspecified"))
    )
    (net (code "46") (name "Net-(U11-A)") (class "Default")
      (node (ref "L4") (pin "2") (pinfunction "2_2") (pintype "unspecified"))
      (node (ref "U11") (pin "2") (pinfunction "A_2") (pintype "unspecified"))
      (node (ref "U7") (pin "1") (pinfunction "SC_1") (pintype "unspecified"))
    )
    (net (code "47") (name "Net-(U11-K)") (class "Default")
      (node (ref "D1") (pin "2") (pinfunction "2_2") (pintype "unspecified"))
      (node (ref "U11") (pin "1") (pinfunction "K_1") (pintype "unspecified"))
    )
    (net (code "48") (name "Net-(U12-A)") (class "Default")
      (node (ref "D1") (pin "1") (pinfunction "1_1") (pintype "unspecified"))
      (node (ref "U12") (pin "2") (pinfunction "A_2") (pintype "unspecified"))
    )
    (net (code "49") (name "Net-(USBC1-CC1)") (class "Default")
      (node (ref "R22") (pin "2") (pinfunction "2_2") (pintype "unspecified"))
      (node (ref "USBC1") (pin "A5") (pinfunction "CC1_A5") (pintype "unspecified"))
    )
    (net (code "50") (name "Net-(USBC1-CC2)") (class "Default")
      (node (ref "R21") (pin "2") (pinfunction "2_2") (pintype "unspecified"))
      (node (ref "USBC1") (pin "B5") (pinfunction "CC2_B5") (pintype "unspecified"))
    )
    (net (code "51") (name "RGB_LED") (class "Default")
      (node (ref "R16") (pin "2") (pinfunction "2_2") (pintype "unspecified"))
      (node (ref "U1") (pin "51") (pinfunction "PA10_51") (pintype "unspecified"))
    )
    (net (code "52") (name "SCL") (class "Default")
      (node (ref "J1") (pin "3") (pinfunction "3_3") (pintype "input"))
      (node (ref "J2") (pin "4") (pinfunction "4_4") (pintype "unspecified"))
      (node (ref "U1") (pin "6") (pinfunction "PB8_6") (pintype "unspecified"))
    )
    (net (code "53") (name "SDA") (class "Default")
      (node (ref "J1") (pin "1") (pinfunction "1_1") (pintype "input"))
      (node (ref "J2") (pin "3") (pinfunction "3_3") (pintype "unspecified"))
      (node (ref "U1") (pin "7") (pinfunction "PB9_7") (pintype "unspecified"))
    )
    (net (code "54") (name "SW3V_MCU") (class "Default")
      (node (ref "Q4") (pin "1") (pinfunction "G_1") (pintype "unspecified"))
      (node (ref "U1") (pin "11") (pinfunction "PC2_11") (pintype "unspecified"))
    )
    (net (code "55") (name "SW5V_MCU") (class "Default")
      (node (ref "Q5") (pin "1") (pinfunction "G_1") (pintype "unspecified"))
      (node (ref "U1") (pin "12") (pinfunction "PC3_12") (pintype "unspecified"))
    )
    (net (code "56") (name "VBAT") (class "Default")
      (node (ref "C24") (pin "1") (pinfunction "1_1") (pintype "unspecified"))
      (node (ref "C28") (pin "2") (pinfunction "2_2") (pintype "unspecified"))
      (node (ref "H2") (pin "1") (pinfunction "1_1") (pintype "input"))
      (node (ref "R13") (pin "1") (pinfunction "1_1") (pintype "unspecified"))
      (node (ref "R14") (pin "1") (pinfunction "1_1") (pintype "unspecified"))
      (node (ref "R23") (pin "2") (pinfunction "2_2") (pintype "unspecified"))
      (node (ref "U10") (pin "3") (pinfunction "IN_3") (pintype "passive"))
      (node (ref "U5") (pin "5") (pinfunction "BAT_5") (pintype "unspecified"))
      (node (ref "U6") (pin "1") (pinfunction "1_1") (pintype "unspecified"))
      (node (ref "U7") (pin "6") (pinfunction "VCC_6") (pintype "unspecified"))
    )
    (net (code "57") (name "VBUS") (class "Default")
      (node (ref "C27") (pin "1") (pinfunction "1_1") (pintype "unspecified"))
      (node (ref "R11") (pin "2") (pinfunction "2_2") (pintype "unspecified"))
      (node (ref "R18") (pin "1") (pinfunction "1_1") (pintype "unspecified"))
      (node (ref "R19") (pin "1") (pinfunction "1_1") (pintype "unspecified"))
      (node (ref "U5") (pin "4") (pinfunction "VCC_4") (pintype "unspecified"))
      (node (ref "U5") (pin "8") (pinfunction "CE_8") (pintype "unspecified"))
      (node (ref "USBC1") (pin "A4B9") (pinfunction "VBUS_A4B9") (pintype "unspecified"))
      (node (ref "USBC1") (pin "B4A9") (pinfunction "VBUS_B4A9") (pintype "unspecified"))
    )
    (net (code "58") (name "VCC") (class "Default")
      (node (ref "C1") (pin "2") (pinfunction "2_2") (pintype "unspecified"))
      (node (ref "C16") (pin "2") (pinfunction "2_2") (pintype "unspecified"))
      (node (ref "C18") (pin "2") (pinfunction "2_2") (pintype "unspecified"))
      (node (ref "C2") (pin "2") (pinfunction "2_2") (pintype "unspecified"))
      (node (ref "C3") (pin "2") (pinfunction "2_2") (pintype "unspecified"))
      (node (ref "C30") (pin "2") (pinfunction "2_2") (pintype "unspecified"))
      (node (ref "C4") (pin "2") (pinfunction "2_2") (pintype "unspecified"))
      (node (ref "H1") (pin "3") (pinfunction "3_3") (pintype "unspecified"))
      (node (ref "KEY1") (pin "2") (pinfunction "2_2") (pintype "unspecified"))
      (node (ref "L2") (pin "2") (pinfunction "2_2") (pintype "unspecified"))
      (node (ref "L3") (pin "2") (pinfunction "2_2") (pintype "unspecified"))
      (node (ref "R27") (pin "2") (pinfunction "2_2") (pintype "unspecified"))
      (node (ref "R3") (pin "2") (pinfunction "2_2") (pintype "unspecified"))
      (node (ref "R7") (pin "1") (pinfunction "1_1") (pintype "unspecified"))
      (node (ref "U1") (pin "1") (pinfunction "VBAT_1") (pintype "unspecified"))
      (node (ref "U1") (pin "33") (pinfunction "VDDRF_33") (pintype "unspecified"))
      (node (ref "X2") (pin "1") (pinfunction "1_1") (pintype "unspecified"))
    )
    (net (code "59") (name "VDD_MCU") (class "Default")
      (node (ref "D2") (pin "2") (pinfunction "2_2") (pintype "unspecified"))
      (node (ref "L1") (pin "1") (pinfunction "1_1") (pintype "unspecified"))
      (node (ref "U1") (pin "30") (pinfunction "VDD_30") (pintype "unspecified"))
      (node (ref "U1") (pin "45") (pinfunction "VDD_45") (pintype "unspecified"))
      (node (ref "U1") (pin "55") (pinfunction "VDDUSB_55") (pintype "unspecified"))
      (node (ref "U1") (pin "68") (pinfunction "VDD_68") (pintype "unspecified"))
    )
    (net (code "60") (name "unconnected-(Q2-D12-Pad1)") (class "Default")
      (node (ref "Q2") (pin "1") (pinfunction "D12_1") (pintype "unspecified"))
    )
    (net (code "61") (name "unconnected-(Q2-D12-Pad8)") (class "Default")
      (node (ref "Q2") (pin "8") (pinfunction "D12_8") (pintype "unspecified"))
    )
    (net (code "62") (name "unconnected-(U1-AT0-Pad36)") (class "Default")
      (node (ref "U1") (pin "36") (pinfunction "AT0_36") (pintype "unspecified"))
    )
    (net (code "63") (name "unconnected-(U1-AT1-Pad37)") (class "Default")
      (node (ref "U1") (pin "37") (pinfunction "AT1_37") (pintype "unspecified"))
    )
    (net (code "64") (name "unconnected-(U1-EP-Pad69)") (class "Default")
      (node (ref "U1") (pin "69") (pinfunction "EP_69") (pintype "unspecified"))
    )
    (net (code "65") (name "unconnected-(U1-PA0-Pad15)") (class "Default")
      (node (ref "U1") (pin "15") (pinfunction "PA0_15") (pintype "unspecified"))
    )
    (net (code "66") (name "unconnected-(U1-PA1-Pad16)") (class "Default")
      (node (ref "U1") (pin "16") (pinfunction "PA1_16") (pintype "unspecified"))
    )
    (net (code "67") (name "unconnected-(U1-PA2-Pad17)") (class "Default")
      (node (ref "U1") (pin "17") (pinfunction "PA2_17") (pintype "unspecified"))
    )
    (net (code "68") (name "unconnected-(U1-PA3-Pad18)") (class "Default")
      (node (ref "U1") (pin "18") (pinfunction "PA3_18") (pintype "unspecified"))
    )
    (net (code "69") (name "unconnected-(U1-PA4-Pad19)") (class "Default")
      (node (ref "U1") (pin "19") (pinfunction "PA4_19") (pintype "unspecified"))
    )
    (net (code "70") (name "unconnected-(U1-PA5-Pad20)") (class "Default")
      (node (ref "U1") (pin "20") (pinfunction "PA5_20") (pintype "unspecified"))
    )
    (net (code "71") (name "unconnected-(U1-PA6-Pad21)") (class "Default")
      (node (ref "U1") (pin "21") (pinfunction "PA6_21") (pintype "unspecified"))
    )
    (net (code "72") (name "unconnected-(U1-PA11-Pad52)") (class "Default")
      (node (ref "U1") (pin "52") (pinfunction "PA11_52") (pintype "unspecified"))
    )
    (net (code "73") (name "unconnected-(U1-PA12-Pad53)") (class "Default")
      (node (ref "U1") (pin "53") (pinfunction "PA12_53") (pintype "unspecified"))
    )
    (net (code "74") (name "unconnected-(U1-PA15-Pad57)") (class "Default")
      (node (ref "U1") (pin "57") (pinfunction "PA15_57") (pintype "unspecified"))
    )
    (net (code "75") (name "unconnected-(U1-PB0-Pad38)") (class "Default")
      (node (ref "U1") (pin "38") (pinfunction "PB0_38") (pintype "unspecified"))
    )
    (net (code "76") (name "unconnected-(U1-PB1-Pad39)") (class "Default")
      (node (ref "U1") (pin "39") (pinfunction "PB1_39") (pintype "unspecified"))
    )
    (net (code "77") (name "unconnected-(U1-PB2-Pad27)") (class "Default")
      (node (ref "U1") (pin "27") (pinfunction "PB2_27") (pintype "unspecified"))
    )
    (net (code "78") (name "unconnected-(U1-PB3-Pad63)") (class "Default")
      (node (ref "U1") (pin "63") (pinfunction "PB3_63") (pintype "unspecified"))
    )
    (net (code "79") (name "unconnected-(U1-PB4-Pad64)") (class "Default")
      (node (ref "U1") (pin "64") (pinfunction "PB4_64") (pintype "unspecified"))
    )
    (net (code "80") (name "unconnected-(U1-PB5-Pad65)") (class "Default")
      (node (ref "U1") (pin "65") (pinfunction "PB5_65") (pintype "unspecified"))
    )
    (net (code "81") (name "unconnected-(U1-PB6-Pad66)") (class "Default")
      (node (ref "U1") (pin "66") (pinfunction "PB6_66") (pintype "unspecified"))
    )
    (net (code "82") (name "unconnected-(U1-PB7-Pad67)") (class "Default")
      (node (ref "U1") (pin "67") (pinfunction "PB7_67") (pintype "unspecified"))
    )
    (net (code "83") (name "unconnected-(U1-PB10-Pad28)") (class "Default")
      (node (ref "U1") (pin "28") (pinfunction "PB10_28") (pintype "unspecified"))
    )
    (net (code "84") (name "unconnected-(U1-PB11-Pad29)") (class "Default")
      (node (ref "U1") (pin "29") (pinfunction "PB11_29") (pintype "unspecified"))
    )
    (net (code "85") (name "unconnected-(U1-PB12-Pad46)") (class "Default")
      (node (ref "U1") (pin "46") (pinfunction "PB12_46") (pintype "unspecified"))
    )
    (net (code "86") (name "unconnected-(U1-PB13-Pad47)") (class "Default")
      (node (ref "U1") (pin "47") (pinfunction "PB13_47") (pintype "unspecified"))
    )
    (net (code "87") (name "unconnected-(U1-PB14-Pad48)") (class "Default")
      (node (ref "U1") (pin "48") (pinfunction "PB14_48") (pintype "unspecified"))
    )
    (net (code "88") (name "unconnected-(U1-PB15-Pad49)") (class "Default")
      (node (ref "U1") (pin "49") (pinfunction "PB15_49") (pintype "unspecified"))
    )
    (net (code "89") (name "unconnected-(U1-PC0-Pad9)") (class "Default")
      (node (ref "U1") (pin "9") (pinfunction "PC0_9") (pintype "unspecified"))
    )
    (net (code "90") (name "unconnected-(U1-PC5-Pad26)") (class "Default")
      (node (ref "U1") (pin "26") (pinfunction "PC5_26") (pintype "unspecified"))
    )
    (net (code "91") (name "unconnected-(U1-PC6-Pad50)") (class "Default")
      (node (ref "U1") (pin "50") (pinfunction "PC6_50") (pintype "unspecified"))
    )
    (net (code "92") (name "unconnected-(U1-PC10-Pad58)") (class "Default")
      (node (ref "U1") (pin "58") (pinfunction "PC10_58") (pintype "unspecified"))
    )
    (net (code "93") (name "unconnected-(U1-PC11-Pad59)") (class "Default")
      (node (ref "U1") (pin "59") (pinfunction "PC11_59") (pintype "unspecified"))
    )
    (net (code "94") (name "unconnected-(U1-PC12-Pad60)") (class "Default")
      (node (ref "U1") (pin "60") (pinfunction "PC12_60") (pintype "unspecified"))
    )
    (net (code "95") (name "unconnected-(U1-PC13-Pad2)") (class "Default")
      (node (ref "U1") (pin "2") (pinfunction "PC13_2") (pintype "unspecified"))
    )
    (net (code "96") (name "unconnected-(U1-PC14-OSC32_IN-Pad3)") (class "Default")
      (node (ref "U1") (pin "3") (pinfunction "PC14-OSC32_IN_3") (pintype "unspecified"))
    )
    (net (code "97") (name "unconnected-(U1-PC15-OSC32_OUT-Pad4)") (class "Default")
      (node (ref "U1") (pin "4") (pinfunction "PC15-OSC32_OUT_4") (pintype "unspecified"))
    )
    (net (code "98") (name "unconnected-(U1-PD0-Pad61)") (class "Default")
      (node (ref "U1") (pin "61") (pinfunction "PD0_61") (pintype "unspecified"))
    )
    (net (code "99") (name "unconnected-(U1-PD1-Pad62)") (class "Default")
      (node (ref "U1") (pin "62") (pinfunction "PD1_62") (pintype "unspecified"))
    )
    (net (code "100") (name "unconnected-(U1-PE4-Pad40)") (class "Default")
      (node (ref "U1") (pin "40") (pinfunction "PE4_40") (pintype "unspecified"))
    )
    (net (code "101") (name "unconnected-(U1-VDDSMPS-Pad44)") (class "Default")
      (node (ref "U1") (pin "44") (pinfunction "VDDSMPS_44") (pintype "unspecified"))
    )
    (net (code "102") (name "unconnected-(U1-VFBSMPS-Pad41)") (class "Default")
      (node (ref "U1") (pin "41") (pinfunction "VFBSMPS_41") (pintype "unspecified"))
    )
    (net (code "103") (name "unconnected-(U1-VLXSMPS-Pad43)") (class "Default")
      (node (ref "U1") (pin "43") (pinfunction "VLXSMPS_43") (pintype "unspecified"))
    )
    (net (code "104") (name "unconnected-(U5-EP-Pad9)") (class "Default")
      (node (ref "U5") (pin "9") (pinfunction "EP_9") (pintype "unspecified"))
    )
    (net (code "105") (name "unconnected-(U5-GND-Pad3)") (class "Default")
      (node (ref "U5") (pin "3") (pinfunction "GND_3") (pintype "unspecified"))
    )
    (net (code "106") (name "unconnected-(U7-FB-Pad5)") (class "Default")
      (node (ref "U7") (pin "5") (pinfunction "FB_5") (pintype "unspecified"))
    )
    (net (code "107") (name "unconnected-(U8-CS-Pad2)") (class "Default")
      (node (ref "U8") (pin "2") (pinfunction "CS_2") (pintype "unspecified"))
    )
    (net (code "108") (name "unconnected-(U8-TD-Pad4)") (class "Default")
      (node (ref "U8") (pin "4") (pinfunction "TD_4") (pintype "unspecified"))
    )
    (net (code "109") (name "unconnected-(U9-DO-Pad2)") (class "Default")
      (node (ref "U9") (pin "2") (pinfunction "DO_2") (pintype "unspecified"))
    )
    (net (code "110") (name "unconnected-(USBC1-DN1-PadA7)") (class "Default")
      (node (ref "USBC1") (pin "A7") (pinfunction "DN1_A7") (pintype "unspecified"))
    )
    (net (code "111") (name "unconnected-(USBC1-DN2-PadB7)") (class "Default")
      (node (ref "USBC1") (pin "B7") (pinfunction "DN2_B7") (pintype "unspecified"))
    )
    (net (code "112") (name "unconnected-(USBC1-DP1-PadA6)") (class "Default")
      (node (ref "USBC1") (pin "A6") (pinfunction "DP1_A6") (pintype "unspecified"))
    )
    (net (code "113") (name "unconnected-(USBC1-DP2-PadB6)") (class "Default")
      (node (ref "USBC1") (pin "B6") (pinfunction "DP2_B6") (pintype "unspecified"))
    )
    (net (code "114") (name "unconnected-(USBC1-SBU1-PadA8)") (class "Default")
      (node (ref "USBC1") (pin "A8") (pinfunction "SBU1_A8") (pintype "unspecified"))
    )
    (net (code "115") (name "unconnected-(USBC1-SUB2-PadB8)") (class "Default")
      (node (ref "USBC1") (pin "B8") (pinfunction "SUB2_B8") (pintype "unspecified"))
    )
  )
)
